# v1.net
KiCad netlist of a schematic drawn in EAGLE
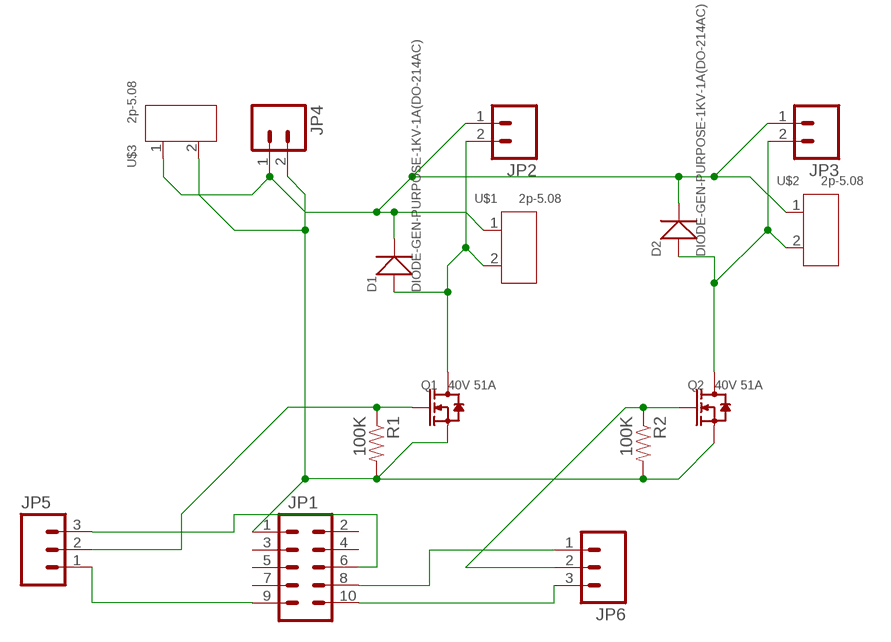
[diagram p0: schematic, sheet 1]

(export (version "E")
  (design (tool "Eeschema 10.0.6"))
  (components
    (comp (ref "D1")
      (value "DIODE-GEN-PURPOSE-1KV-1A(DO-214AC)")
      (footprint "eagle-import:DO-214AC")
      (fields (field (name "MPN") "1N4007"))
      (libsource (lib "eagle-import") (part "DIODE-GEN-PURPOSE-1KV-1A(DO-214AC)"))
    )
    (comp (ref "D2")
      (value "DIODE-GEN-PURPOSE-1KV-1A(DO-214AC)")
      (footprint "eagle-import:DO-214AC")
      (fields (field (name "MPN") "1N4007"))
      (libsource (lib "eagle-import") (part "DIODE-GEN-PURPOSE-1KV-1A(DO-214AC)"))
    )
    (comp (ref "JP1")
      (value "M05X2PTH")
      (footprint "eagle-import:AVR_ICSP")
      (libsource (lib "eagle-import") (part "M05X2PTH"))
    )
    (comp (ref "JP2")
      (value "M02POLAR")
      (footprint "eagle-import:MOLEX-1X2")
      (libsource (lib "eagle-import") (part "M02POLAR"))
    )
    (comp (ref "JP3")
      (value "M02POLAR")
      (footprint "eagle-import:MOLEX-1X2")
      (libsource (lib "eagle-import") (part "M02POLAR"))
    )
    (comp (ref "JP4")
      (value "M02POLAR")
      (footprint "eagle-import:MOLEX-1X2")
      (libsource (lib "eagle-import") (part "M02POLAR"))
    )
    (comp (ref "JP5")
      (value "M03PTH")
      (footprint "eagle-import:1X03")
      (libsource (lib "eagle-import") (part "M03PTH"))
    )
    (comp (ref "JP6")
      (value "M03PTH")
      (footprint "eagle-import:1X03")
      (libsource (lib "eagle-import") (part "M03PTH"))
    )
    (comp (ref "Q1")
      (value "40V 51A")
      (footprint "eagle-import:DPAK")
      (fields (field (name "MPN") "NTD5805NT4G"))
      (libsource (lib "eagle-import") (part "SMD-MOSFET-HIGH-POWER-N-CH-40V-51A(DPAK)"))
    )
    (comp (ref "Q2")
      (value "40V 51A")
      (footprint "eagle-import:DPAK")
      (fields (field (name "MPN") "NTD5805NT4G"))
      (libsource (lib "eagle-import") (part "SMD-MOSFET-HIGH-POWER-N-CH-40V-51A(DPAK)"))
    )
    (comp (ref "R1")
      (value "100K")
      (footprint "eagle-import:0805")
      (libsource (lib "eagle-import") (part "RESISTOR0805-RES"))
    )
    (comp (ref "R2")
      (value "100K")
      (footprint "eagle-import:0805")
      (libsource (lib "eagle-import") (part "RESISTOR0805-RES"))
    )
    (comp (ref "U$1")
      (value "2p-5.08")
      (footprint "eagle-import:H2-5.0-10.5X8.0MM")
      (fields (field (name "MPN") "GS009S-2P-2"))
      (libsource (lib "eagle-import") (part "DIP-BLUE-SCREW-TERMINAL(2P-5.08)"))
    )
    (comp (ref "U$2")
      (value "2p-5.08")
      (footprint "eagle-import:H2-5.0-10.5X8.0MM")
      (fields (field (name "MPN") "GS009S-2P-2"))
      (libsource (lib "eagle-import") (part "DIP-BLUE-SCREW-TERMINAL(2P-5.08)"))
    )
    (comp (ref "U$3")
      (value "2p-5.08")
      (footprint "eagle-import:H2-5.0-10.5X8.0MM")
      (fields (field (name "MPN") "GS009S-2P-2"))
      (libsource (lib "eagle-import") (part "DIP-BLUE-SCREW-TERMINAL(2P-5.08)"))
    )
  )
  (nets
    (net (code "1") (name "Net-(D1-+)") (class "Default")
      (node (ref "D1") (pin "1") (pinfunction "+_1") (pintype "passive"))
      (node (ref "JP2") (pin "2") (pinfunction "2_2") (pintype "passive"))
      (node (ref "Q1") (pin "3") (pinfunction "D_3") (pintype "passive"))
      (node (ref "U$1") (pin "2") (pinfunction "2_2") (pintype "bidirectional"))
    )
    (net (code "2") (name "Net-(D1--)") (class "Default")
      (node (ref "D1") (pin "2") (pinfunction "-_2") (pintype "passive"))
      (node (ref "D2") (pin "2") (pinfunction "-_2") (pintype "passive"))
      (node (ref "JP2") (pin "1") (pinfunction "1_1") (pintype "passive"))
      (node (ref "JP3") (pin "1") (pinfunction "1_1") (pintype "passive"))
      (node (ref "JP4") (pin "1") (pinfunction "1_1") (pintype "passive"))
      (node (ref "U$1") (pin "1") (pinfunction "1_1") (pintype "bidirectional"))
      (node (ref "U$2") (pin "1") (pinfunction "1_1") (pintype "bidirectional"))
      (node (ref "U$3") (pin "1") (pinfunction "1_1") (pintype "bidirectional"))
    )
    (net (code "3") (name "Net-(D2-+)") (class "Default")
      (node (ref "D2") (pin "1") (pinfunction "+_1") (pintype "passive"))
      (node (ref "JP3") (pin "2") (pinfunction "2_2") (pintype "passive"))
      (node (ref "Q2") (pin "3") (pinfunction "D_3") (pintype "passive"))
      (node (ref "U$2") (pin "2") (pinfunction "2_2") (pintype "bidirectional"))
    )
    (net (code "4") (name "Net-(JP1-Pad6)") (class "Default")
      (node (ref "JP1") (pin "6") (pinfunction "6_6") (pintype "passive"))
      (node (ref "JP5") (pin "3") (pinfunction "3_3") (pintype "passive"))
    )
    (net (code "5") (name "Net-(JP1-Pad8)") (class "Default")
      (node (ref "JP1") (pin "8") (pinfunction "8_8") (pintype "passive"))
      (node (ref "JP6") (pin "1") (pinfunction "1_1") (pintype "passive"))
    )
    (net (code "6") (name "Net-(JP1-Pad9)") (class "Default")
      (node (ref "JP1") (pin "9") (pinfunction "9_9") (pintype "passive"))
      (node (ref "JP5") (pin "1") (pinfunction "1_1") (pintype "passive"))
    )
    (net (code "7") (name "Net-(JP1-Pad10)") (class "Default")
      (node (ref "JP1") (pin "10") (pinfunction "10_10") (pintype "passive"))
      (node (ref "JP6") (pin "3") (pinfunction "3_3") (pintype "passive"))
    )
    (net (code "8") (name "Net-(Q1-G)") (class "Default")
      (node (ref "JP5") (pin "2") (pinfunction "2_2") (pintype "passive"))
      (node (ref "Q1") (pin "1") (pinfunction "G_1") (pintype "passive"))
      (node (ref "R1") (pin "1") (pinfunction "1_1") (pintype "passive"))
    )
    (net (code "9") (name "Net-(Q1-S)") (class "Default")
      (node (ref "JP1") (pin "1") (pinfunction "1_1") (pintype "passive"))
      (node (ref "JP4") (pin "2") (pinfunction "2_2") (pintype "passive"))
      (node (ref "Q1") (pin "2") (pinfunction "S_2") (pintype "passive"))
      (node (ref "Q2") (pin "2") (pinfunction "S_2") (pintype "passive"))
      (node (ref "R1") (pin "2") (pinfunction "2_2") (pintype "passive"))
      (node (ref "R2") (pin "2") (pinfunction "2_2") (pintype "passive"))
      (node (ref "U$3") (pin "2") (pinfunction "2_2") (pintype "bidirectional"))
    )
    (net (code "10") (name "Net-(Q2-G)") (class "Default")
      (node (ref "JP6") (pin "2") (pinfunction "2_2") (pintype "passive"))
      (node (ref "Q2") (pin "1") (pinfunction "G_1") (pintype "passive"))
      (node (ref "R2") (pin "1") (pinfunction "1_1") (pintype "passive"))
    )
    (net (code "11") (name "unconnected-(JP1-Pad2)") (class "Default")
      (node (ref "JP1") (pin "2") (pinfunction "2_2") (pintype "passive"))
    )
    (net (code "12") (name "unconnected-(JP1-Pad3)") (class "Default")
      (node (ref "JP1") (pin "3") (pinfunction "3_3") (pintype "passive"))
    )
    (net (code "13") (name "unconnected-(JP1-Pad4)") (class "Default")
      (node (ref "JP1") (pin "4") (pinfunction "4_4") (pintype "passive"))
    )
    (net (code "14") (name "unconnected-(JP1-Pad5)") (class "Default")
      (node (ref "JP1") (pin "5") (pinfunction "5_5") (pintype "passive"))
    )
    (net (code "15") (name "unconnected-(JP1-Pad7)") (class "Default")
      (node (ref "JP1") (pin "7") (pinfunction "7_7") (pintype "passive"))
    )
  )
)
